# blinky.net
KiCad netlist of a schematic drawn in EAGLE
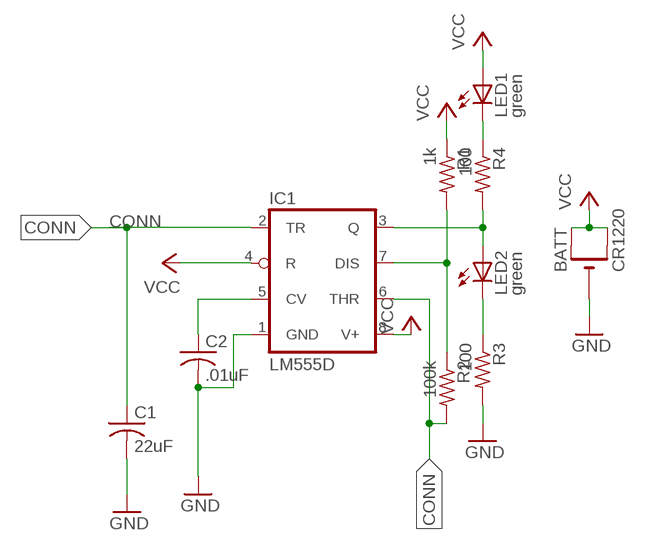
[diagram p0: schematic, sheet 1]

(export (version "E")
  (design (tool "Eeschema 10.0.6"))
  (components
    (comp (ref "BATT")
      (value "CR1220")
      (footprint "eagle-import:CR1220-SMD")
      (libsource (lib "eagle-import") (part "CR1220SMT"))
    )
    (comp (ref "C1")
      (value "22uF")
      (footprint "eagle-import:C0805")
      (fields (field (name "MPN") "MC0805B224K500A5.08MM"))
      (libsource (lib "eagle-import") (part "C-USC0805"))
    )
    (comp (ref "C2")
      (value ".01uF")
      (footprint "eagle-import:C0805")
      (fields (field (name "MPN") "26884"))
      (libsource (lib "eagle-import") (part "C-USC0805"))
    )
    (comp (ref "IC1")
      (value "LM555D")
      (footprint "eagle-import:SO08")
      (fields (field (name "MPN") "TLC555CP"))
      (libsource (lib "eagle-import") (part "555DLM"))
    )
    (comp (ref "LED1")
      (value "green")
      (footprint "eagle-import:CHIPLED_0805")
      (fields (field (name "MPN") "MCL-S270GC"))
      (libsource (lib "eagle-import") (part "LEDCHIPLED_0805"))
    )
    (comp (ref "LED2")
      (value "green")
      (footprint "eagle-import:CHIPLED_0805")
      (fields (field (name "MPN") "MCL-S270GC"))
      (libsource (lib "eagle-import") (part "LEDCHIPLED_0805"))
    )
    (comp (ref "R1")
      (value "1k")
      (footprint "eagle-import:R0805")
      (fields (field (name "MPN") "ERJ-1GNF1001C"))
      (libsource (lib "eagle-import") (part "R-US_R0805"))
    )
    (comp (ref "R2")
      (value "100k")
      (footprint "eagle-import:R0805")
      (fields (field (name "MPN") "MCTF0805BTC1003"))
      (libsource (lib "eagle-import") (part "R-US_R0805"))
    )
    (comp (ref "R3")
      (value "100")
      (footprint "eagle-import:R0805")
      (fields (field (name "MF") "VISHAY/DALE") (field (name "MPN") "CRCW080510R0FKEA"))
      (libsource (lib "eagle-import") (part "R-US_R0805"))
    )
    (comp (ref "R4")
      (value "100")
      (footprint "eagle-import:R0805")
      (fields (field (name "MF") "VISHAY/DALE") (field (name "MPN") "CRCW080510R0FKEA"))
      (libsource (lib "eagle-import") (part "R-US_R0805"))
    )
  )
  (nets
    (net (code "1") (name "CONN") (class "Default")
      (node (ref "C1") (pin "1") (pinfunction "1_1") (pintype "passive"))
      (node (ref "IC1") (pin "2") (pinfunction "TR_2") (pintype "input"))
      (node (ref "IC1") (pin "6") (pinfunction "THR_6") (pintype "input"))
      (node (ref "R2") (pin "2") (pinfunction "2_2") (pintype "passive"))
    )
    (net (code "2") (name "GND") (class "Default")
      (node (ref "BATT") (pin "-") (pinfunction "-_-") (pintype "passive"))
      (node (ref "C1") (pin "2") (pinfunction "2_2") (pintype "passive"))
      (node (ref "C2") (pin "2") (pinfunction "2_2") (pintype "passive"))
      (node (ref "IC1") (pin "1") (pinfunction "GND_1") (pintype "power_in"))
      (node (ref "R3") (pin "2") (pinfunction "2_2") (pintype "passive"))
    )
    (net (code "3") (name "Net-(IC1-CV)") (class "Default")
      (node (ref "C2") (pin "1") (pinfunction "1_1") (pintype "passive"))
      (node (ref "IC1") (pin "5") (pinfunction "CV_5") (pintype "input"))
    )
    (net (code "4") (name "Net-(IC1-DIS)") (class "Default")
      (node (ref "IC1") (pin "7") (pinfunction "DIS_7") (pintype "input"))
      (node (ref "R1") (pin "2") (pinfunction "2_2") (pintype "passive"))
      (node (ref "R2") (pin "1") (pinfunction "1_1") (pintype "passive"))
    )
    (net (code "5") (name "Net-(IC1-Q)") (class "Default")
      (node (ref "IC1") (pin "3") (pinfunction "Q_3") (pintype "output"))
      (node (ref "LED2") (pin "A") (pinfunction "A_A") (pintype "passive"))
      (node (ref "R4") (pin "2") (pinfunction "2_2") (pintype "passive"))
    )
    (net (code "6") (name "Net-(LED1-PadC)") (class "Default")
      (node (ref "LED1") (pin "C") (pinfunction "C_C") (pintype "passive"))
      (node (ref "R4") (pin "1") (pinfunction "1_1") (pintype "passive"))
    )
    (net (code "7") (name "Net-(LED2-PadC)") (class "Default")
      (node (ref "LED2") (pin "C") (pinfunction "C_C") (pintype "passive"))
      (node (ref "R3") (pin "1") (pinfunction "1_1") (pintype "passive"))
    )
    (net (code "8") (name "VCC") (class "Default")
      (node (ref "BATT") (pin "+$1") (pinfunction "+_+$1") (pintype "passive"))
      (node (ref "BATT") (pin "+$2") (pinfunction "+1_+$2") (pintype "passive"))
      (node (ref "IC1") (pin "4") (pinfunction "R_4") (pintype "input"))
      (node (ref "IC1") (pin "8") (pinfunction "V+_8") (pintype "power_in"))
      (node (ref "LED1") (pin "A") (pinfunction "A_A") (pintype "passive"))
      (node (ref "R1") (pin "1") (pinfunction "1_1") (pintype "passive"))
    )
  )
)
